# bmsMaster_main.net
KiCad netlist of a schematic drawn in Altium Designer
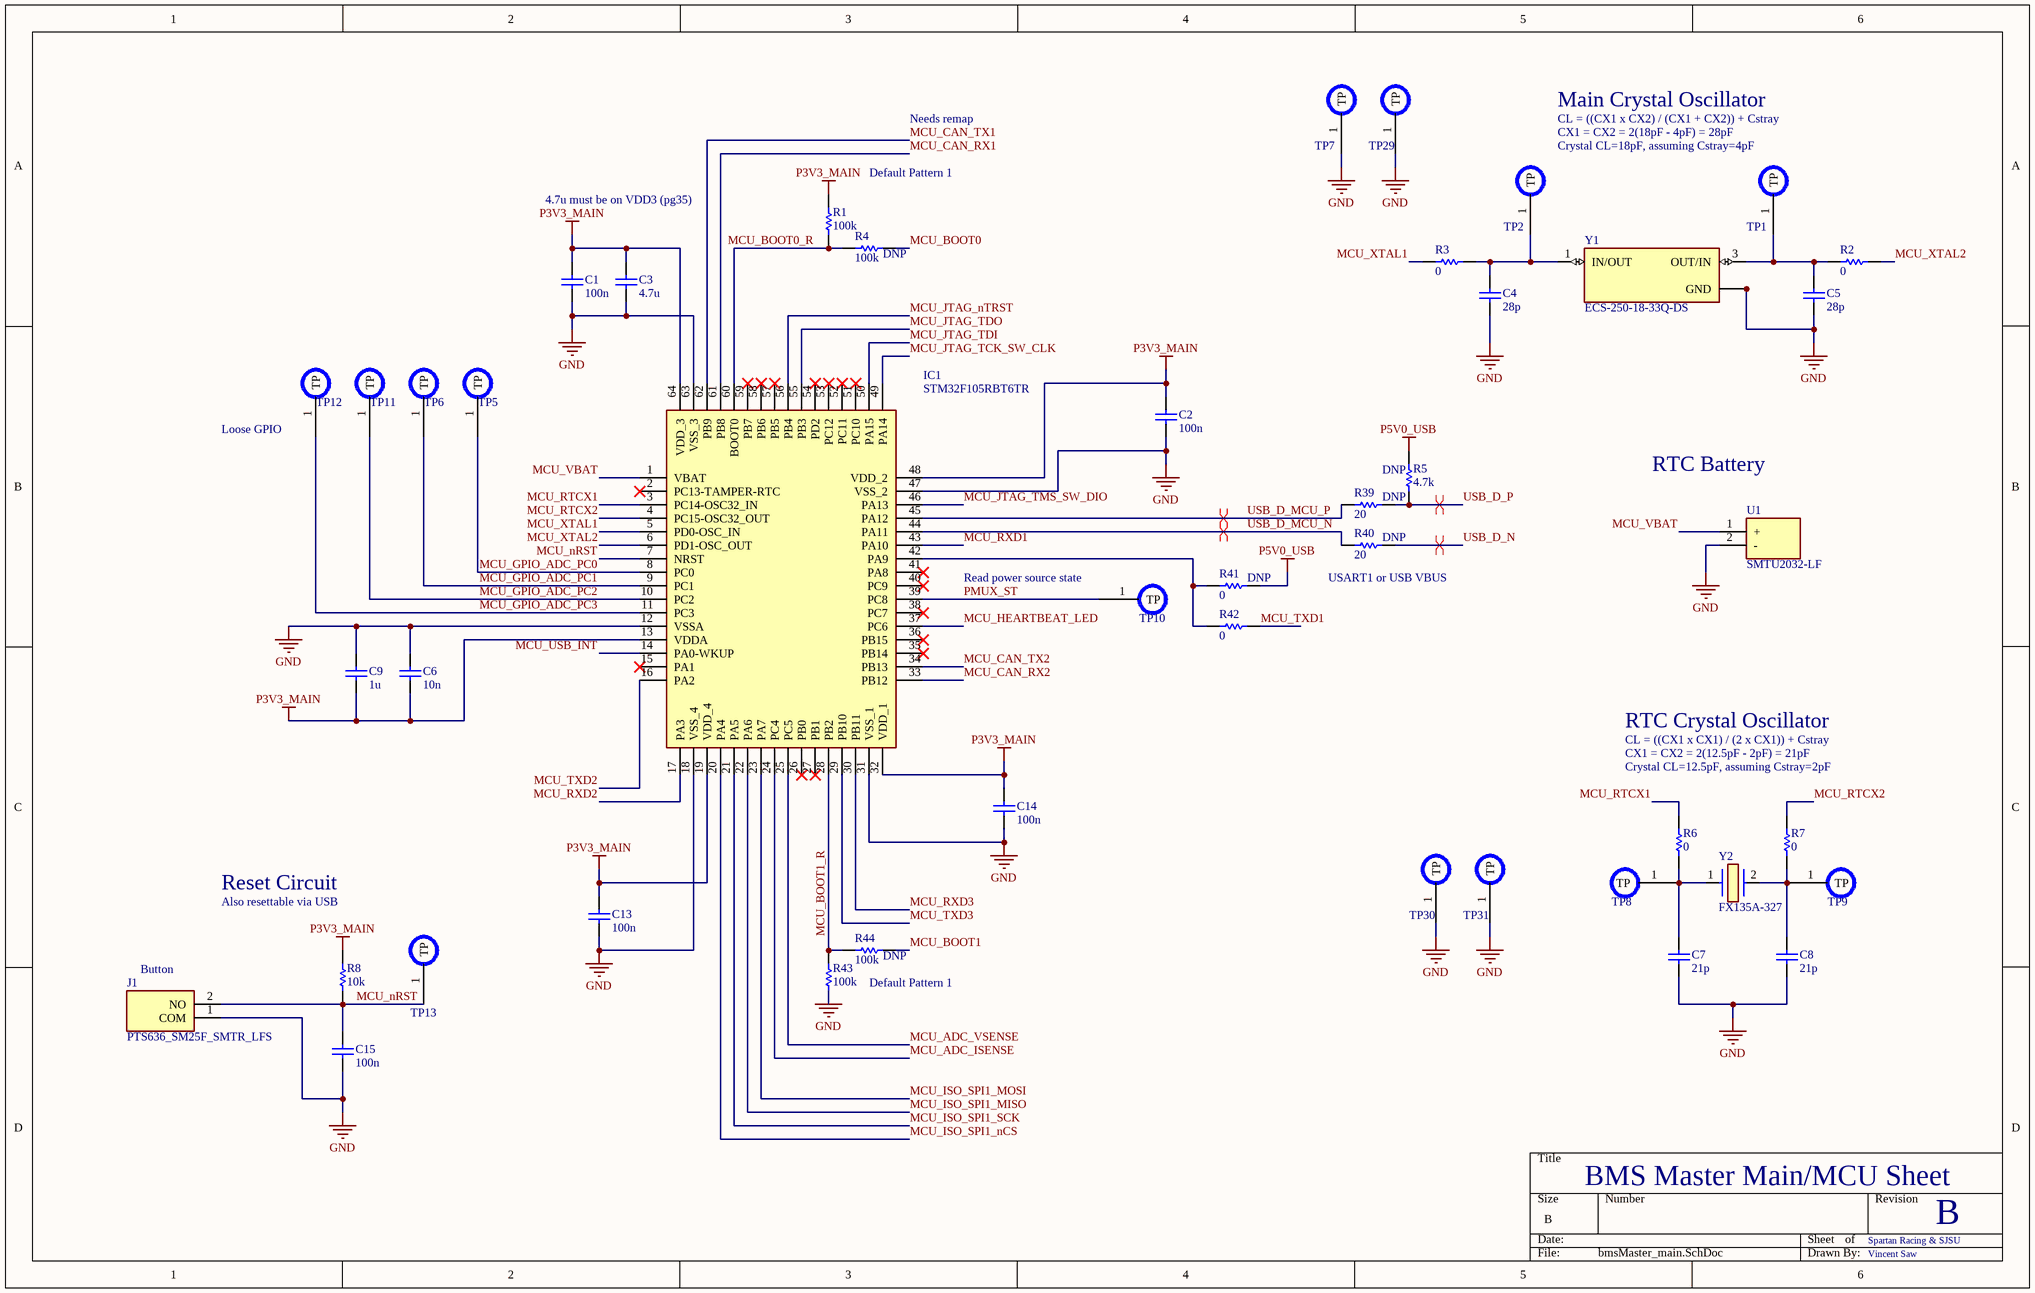
[diagram p0: bmsMaster_main.SchDoc]

(export (version "E")
  (design (tool "Eeschema 10.0.6"))
  (components
    (comp (ref "C1")
      (value "100n")
      (footprint "CAPC1608X90N")
      (description "Capacitor")
      (libsource (lib "Simulation Generic Components") (part "Capacitor"))
    )
    (comp (ref "C2")
      (value "100n")
      (footprint "CAPC1608X90N")
      (description "Capacitor")
      (libsource (lib "Simulation Generic Components") (part "Capacitor"))
    )
    (comp (ref "C3")
      (value "4.7u")
      (footprint "CAPC1608X90N")
      (description "Capacitor")
      (libsource (lib "Simulation Generic Components") (part "Capacitor"))
    )
    (comp (ref "C4")
      (value "28p")
      (footprint "CAPC1608X90N")
      (description "Capacitor")
      (libsource (lib "Simulation Generic Components") (part "Capacitor"))
    )
    (comp (ref "C5")
      (value "28p")
      (footprint "CAPC1608X90N")
      (description "Capacitor")
      (libsource (lib "Simulation Generic Components") (part "Capacitor"))
    )
    (comp (ref "C6")
      (value "10n")
      (footprint "CAPC1608X90N")
      (description "Capacitor")
      (libsource (lib "Simulation Generic Components") (part "Capacitor"))
    )
    (comp (ref "C7")
      (value "21p")
      (footprint "CAPC1608X90N")
      (description "Capacitor")
      (libsource (lib "Simulation Generic Components") (part "Capacitor"))
    )
    (comp (ref "C8")
      (value "21p")
      (footprint "CAPC1608X90N")
      (description "Capacitor")
      (libsource (lib "Simulation Generic Components") (part "Capacitor"))
    )
    (comp (ref "C9")
      (value "1u")
      (footprint "CAPC1608X90N")
      (description "Capacitor")
      (libsource (lib "Simulation Generic Components") (part "Capacitor"))
    )
    (comp (ref "C13")
      (value "100n")
      (footprint "CAPC1608X90N")
      (description "Capacitor")
      (libsource (lib "Simulation Generic Components") (part "Capacitor"))
    )
    (comp (ref "C14")
      (value "100n")
      (footprint "CAPC1608X90N")
      (description "Capacitor")
      (libsource (lib "Simulation Generic Components") (part "Capacitor"))
    )
    (comp (ref "C15")
      (value "100n")
      (footprint "CAPC1608X90N")
      (description "Capacitor")
      (libsource (lib "Simulation Generic Components") (part "Capacitor"))
    )
    (comp (ref "IC1")
      (value "STM32F105RBT6TR")
      (footprint "SamacSys:QFP50P1200X1200X160-64N")
      (description "Integrated Circuit")
      (fields (field (name "MOUSER PART NUMBER") "511-STM32F105RBT6TR"))
      (libsource (lib "*") (part "STM32F105RBT6TR"))
    )
    (comp (ref "J1")
      (value "PTS636_SM25F_SMTR_LFS")
      (footprint "SamacSys:PTS636SM25FSMTRLFS")
      (description "Connector")
      (fields
        (field (name "MANUFACTURER_PART_NUMBER") "PTS636 SM25F SMTR LFS")
        (field (name "MOUSER PART NUMBER") "611-PTS636SM25FSMTRL")
      )
      (libsource (lib "*") (part "PTS636_SM25F_SMTR_LFS"))
    )
    (comp (ref "R1")
      (value "100k")
      (footprint "RESC1608X50N")
      (description "Resistor")
      (libsource (lib "Simulation Generic Components") (part "Resistor"))
    )
    (comp (ref "R2")
      (value "0")
      (footprint "RESC1608X50N")
      (description "Resistor")
      (libsource (lib "Simulation Generic Components") (part "Resistor"))
    )
    (comp (ref "R3")
      (value "0")
      (footprint "RESC1608X50N")
      (description "Resistor")
      (libsource (lib "Simulation Generic Components") (part "Resistor"))
    )
    (comp (ref "R4")
      (value "100k")
      (footprint "RESC1608X50N")
      (description "Resistor")
      (libsource (lib "Simulation Generic Components") (part "Resistor"))
    )
    (comp (ref "R5")
      (value "4.7k")
      (footprint "RESC1608X50N")
      (description "Resistor")
      (libsource (lib "Simulation Generic Components") (part "Resistor"))
    )
    (comp (ref "R6")
      (value "0")
      (footprint "RESC1608X50N")
      (description "Resistor")
      (libsource (lib "Simulation Generic Components") (part "Resistor"))
    )
    (comp (ref "R7")
      (value "0")
      (footprint "RESC1608X50N")
      (description "Resistor")
      (libsource (lib "Simulation Generic Components") (part "Resistor"))
    )
    (comp (ref "R8")
      (value "10k")
      (footprint "RESC1608X50N")
      (description "Resistor")
      (libsource (lib "Simulation Generic Components") (part "Resistor"))
    )
    (comp (ref "R39")
      (value "20")
      (footprint "RESC1608X50N")
      (description "Resistor")
      (libsource (lib "Simulation Generic Components") (part "Resistor"))
    )
    (comp (ref "R40")
      (value "20")
      (footprint "RESC1608X50N")
      (description "Resistor")
      (libsource (lib "Simulation Generic Components") (part "Resistor"))
    )
    (comp (ref "R41")
      (value "0")
      (footprint "RESC1608X50N")
      (description "Resistor")
      (libsource (lib "Simulation Generic Components") (part "Resistor"))
    )
    (comp (ref "R42")
      (value "0")
      (footprint "RESC1608X50N")
      (description "Resistor")
      (libsource (lib "Simulation Generic Components") (part "Resistor"))
    )
    (comp (ref "R43")
      (value "100k")
      (footprint "RESC1608X50N")
      (description "Resistor")
      (libsource (lib "Simulation Generic Components") (part "Resistor"))
    )
    (comp (ref "R44")
      (value "100k")
      (footprint "RESC1608X50N")
      (description "Resistor")
      (libsource (lib "Simulation Generic Components") (part "Resistor"))
    )
    (comp (ref "TP1")
      (value "TSTPT")
      (footprint "Testpoint1")
      (libsource (lib "testpoint1") (part "Testpoint1"))
    )
    (comp (ref "TP2")
      (value "TSTPT")
      (footprint "Testpoint1")
      (libsource (lib "testpoint1") (part "Testpoint1"))
    )
    (comp (ref "TP5")
      (value "TSTPT")
      (footprint "Testpoint1")
      (libsource (lib "testpoint1") (part "Testpoint1"))
    )
    (comp (ref "TP6")
      (value "TSTPT")
      (footprint "Testpoint1")
      (libsource (lib "testpoint1") (part "Testpoint1"))
    )
    (comp (ref "TP7")
      (value "TSTPT")
      (footprint "Testpoint1")
      (libsource (lib "testpoint1") (part "Testpoint1"))
    )
    (comp (ref "TP8")
      (value "TSTPT")
      (footprint "Testpoint1")
      (libsource (lib "testpoint1") (part "Testpoint1"))
    )
    (comp (ref "TP9")
      (value "TSTPT")
      (footprint "Testpoint1")
      (libsource (lib "testpoint1") (part "Testpoint1"))
    )
    (comp (ref "TP10")
      (value "TSTPT")
      (footprint "Testpoint1")
      (libsource (lib "testpoint1") (part "Testpoint1"))
    )
    (comp (ref "TP11")
      (value "TSTPT")
      (footprint "Testpoint1")
      (libsource (lib "testpoint1") (part "Testpoint1"))
    )
    (comp (ref "TP12")
      (value "TSTPT")
      (footprint "Testpoint1")
      (libsource (lib "testpoint1") (part "Testpoint1"))
    )
    (comp (ref "TP13")
      (value "TSTPT")
      (footprint "Testpoint1")
      (libsource (lib "testpoint1") (part "Testpoint1"))
    )
    (comp (ref "TP29")
      (value "TSTPT")
      (footprint "Testpoint1")
      (libsource (lib "testpoint1") (part "Testpoint1"))
    )
    (comp (ref "TP30")
      (value "TSTPT")
      (footprint "Testpoint1")
      (libsource (lib "testpoint1") (part "Testpoint1"))
    )
    (comp (ref "TP31")
      (value "TSTPT")
      (footprint "Testpoint1")
      (libsource (lib "testpoint1") (part "Testpoint1"))
    )
    (comp (ref "U1")
      (value "SMTU2032-LF")
      (footprint "SamacSys:SMTU2032LF")
      (description "Undefined or Miscellaneous")
      (fields (field (name "MOUSER PART NUMBER") "614-SMTU2032-LF"))
      (libsource (lib "*") (part "SMTU2032-LF"))
    )
    (comp (ref "Y1")
      (value "ECS-250-18-33Q-DS")
      (footprint "ECS-250-18-33Q-DS:XTAL_ECS-250-18-33Q-DS")
      (fields (field (name "MF") "{'manufacturer': u'ECS Inc.'}"))
      (libsource (lib "*") (part "ECS-250-18-33Q-DS"))
    )
    (comp (ref "Y2")
      (value "FX135A-327")
      (footprint "SamacSys:FX135A327")
      (description "Crystal or Oscillator")
      (fields (field (name "MOUSER PART NUMBER") "559-FX135A-327"))
      (libsource (lib "*") (part "FX135A-327"))
    )
  )
  (nets
    (net (code "1") (name "/MCU_ADC_ISENSE") (class "Default")
      (node (ref "IC1") (pin "24") (pinfunction "PC4_24") (pintype "passive"))
    )
    (net (code "2") (name "/MCU_ADC_VSENSE") (class "Default")
      (node (ref "IC1") (pin "25") (pinfunction "PC5_25") (pintype "passive"))
    )
    (net (code "3") (name "/MCU_BOOT0") (class "Default")
      (node (ref "R4") (pin "2") (pinfunction "2_2") (pintype "passive"))
    )
    (net (code "4") (name "/MCU_BOOT0_R") (class "Default")
      (node (ref "IC1") (pin "60") (pinfunction "BOOT0_60") (pintype "passive"))
      (node (ref "R1") (pin "1") (pinfunction "1_1") (pintype "passive"))
      (node (ref "R4") (pin "1") (pinfunction "1_1") (pintype "passive"))
    )
    (net (code "5") (name "/MCU_BOOT1") (class "Default")
      (node (ref "R44") (pin "1") (pinfunction "1_1") (pintype "passive"))
    )
    (net (code "6") (name "/MCU_BOOT1_R") (class "Default")
      (node (ref "IC1") (pin "28") (pinfunction "PB2_28") (pintype "passive"))
      (node (ref "R43") (pin "1") (pinfunction "1_1") (pintype "passive"))
      (node (ref "R44") (pin "2") (pinfunction "2_2") (pintype "passive"))
    )
    (net (code "7") (name "/MCU_CAN_RX1") (class "Default")
      (node (ref "IC1") (pin "61") (pinfunction "PB8_61") (pintype "passive"))
    )
    (net (code "8") (name "/MCU_CAN_RX2") (class "Default")
      (node (ref "IC1") (pin "33") (pinfunction "PB12_33") (pintype "passive"))
    )
    (net (code "9") (name "/MCU_CAN_TX1") (class "Default")
      (node (ref "IC1") (pin "62") (pinfunction "PB9_62") (pintype "passive"))
    )
    (net (code "10") (name "/MCU_CAN_TX2") (class "Default")
      (node (ref "IC1") (pin "34") (pinfunction "PB13_34") (pintype "passive"))
    )
    (net (code "11") (name "/MCU_GPIO_ADC_PC0") (class "Default")
      (node (ref "IC1") (pin "8") (pinfunction "PC0_8") (pintype "passive"))
      (node (ref "TP5") (pin "1") (pinfunction "TP_1") (pintype "passive"))
    )
    (net (code "12") (name "/MCU_GPIO_ADC_PC1") (class "Default")
      (node (ref "IC1") (pin "9") (pinfunction "PC1_9") (pintype "passive"))
      (node (ref "TP6") (pin "1") (pinfunction "TP_1") (pintype "passive"))
    )
    (net (code "13") (name "/MCU_GPIO_ADC_PC2") (class "Default")
      (node (ref "IC1") (pin "10") (pinfunction "PC2_10") (pintype "passive"))
      (node (ref "TP11") (pin "1") (pinfunction "TP_1") (pintype "passive"))
    )
    (net (code "14") (name "/MCU_GPIO_ADC_PC3") (class "Default")
      (node (ref "IC1") (pin "11") (pinfunction "PC3_11") (pintype "passive"))
      (node (ref "TP12") (pin "1") (pinfunction "TP_1") (pintype "passive"))
    )
    (net (code "15") (name "/MCU_HEARTBEAT_LED") (class "Default")
      (node (ref "IC1") (pin "37") (pinfunction "PC6_37") (pintype "passive"))
    )
    (net (code "16") (name "/MCU_ISO_SPI1_MISO") (class "Default")
      (node (ref "IC1") (pin "22") (pinfunction "PA6_22") (pintype "passive"))
    )
    (net (code "17") (name "/MCU_ISO_SPI1_MOSI") (class "Default")
      (node (ref "IC1") (pin "23") (pinfunction "PA7_23") (pintype "passive"))
    )
    (net (code "18") (name "/MCU_ISO_SPI1_SCK") (class "Default")
      (node (ref "IC1") (pin "21") (pinfunction "PA5_21") (pintype "passive"))
    )
    (net (code "19") (name "/MCU_ISO_SPI1_nCS") (class "Default")
      (node (ref "IC1") (pin "20") (pinfunction "PA4_20") (pintype "passive"))
    )
    (net (code "20") (name "/MCU_JTAG_TCK_SW_CLK") (class "Default")
      (node (ref "IC1") (pin "49") (pinfunction "PA14_49") (pintype "passive"))
    )
    (net (code "21") (name "/MCU_JTAG_TDI") (class "Default")
      (node (ref "IC1") (pin "50") (pinfunction "PA15_50") (pintype "passive"))
    )
    (net (code "22") (name "/MCU_JTAG_TDO") (class "Default")
      (node (ref "IC1") (pin "55") (pinfunction "PB3_55") (pintype "passive"))
    )
    (net (code "23") (name "/MCU_JTAG_TMS_SW_DIO") (class "Default")
      (node (ref "IC1") (pin "46") (pinfunction "PA13_46") (pintype "passive"))
    )
    (net (code "24") (name "/MCU_JTAG_nTRST") (class "Default")
      (node (ref "IC1") (pin "56") (pinfunction "PB4_56") (pintype "passive"))
    )
    (net (code "25") (name "/MCU_RTCX1") (class "Default")
      (node (ref "IC1") (pin "3") (pinfunction "PC14-OSC32_IN_3") (pintype "passive"))
      (node (ref "R6") (pin "1") (pinfunction "1_1") (pintype "passive"))
    )
    (net (code "26") (name "/MCU_RTCX2") (class "Default")
      (node (ref "IC1") (pin "4") (pinfunction "PC15-OSC32_OUT_4") (pintype "passive"))
      (node (ref "R7") (pin "1") (pinfunction "1_1") (pintype "passive"))
    )
    (net (code "27") (name "/MCU_RXD1") (class "Default")
      (node (ref "IC1") (pin "43") (pinfunction "PA10_43") (pintype "passive"))
    )
    (net (code "28") (name "/MCU_RXD2") (class "Default")
      (node (ref "IC1") (pin "17") (pinfunction "PA3_17") (pintype "passive"))
    )
    (net (code "29") (name "/MCU_RXD3") (class "Default")
      (node (ref "IC1") (pin "30") (pinfunction "PB11_30") (pintype "passive"))
    )
    (net (code "30") (name "/MCU_TXD1") (class "Default")
      (node (ref "R42") (pin "2") (pinfunction "2_2") (pintype "passive"))
    )
    (net (code "31") (name "/MCU_TXD2") (class "Default")
      (node (ref "IC1") (pin "16") (pinfunction "PA2_16") (pintype "passive"))
    )
    (net (code "32") (name "/MCU_TXD3") (class "Default")
      (node (ref "IC1") (pin "29") (pinfunction "PB10_29") (pintype "passive"))
    )
    (net (code "33") (name "/MCU_USB_INT") (class "Default")
      (node (ref "IC1") (pin "14") (pinfunction "PA0-WKUP_14") (pintype "passive"))
    )
    (net (code "34") (name "/MCU_VBAT") (class "Default")
      (node (ref "IC1") (pin "1") (pinfunction "VBAT_1") (pintype "passive"))
      (node (ref "U1") (pin "1") (pinfunction "+_1") (pintype "passive"))
    )
    (net (code "35") (name "/MCU_XTAL1") (class "Default")
      (node (ref "IC1") (pin "5") (pinfunction "PD0-OSC_IN_5") (pintype "passive"))
      (node (ref "R3") (pin "2") (pinfunction "2_2") (pintype "passive"))
    )
    (net (code "36") (name "/MCU_XTAL2") (class "Default")
      (node (ref "IC1") (pin "6") (pinfunction "PD1-OSC_OUT_6") (pintype "passive"))
      (node (ref "R2") (pin "1") (pinfunction "1_1") (pintype "passive"))
    )
    (net (code "37") (name "/MCU_nRST") (class "Default")
      (node (ref "C15") (pin "2") (pinfunction "2_2") (pintype "passive"))
      (node (ref "IC1") (pin "7") (pinfunction "NRST_7") (pintype "passive"))
      (node (ref "J1") (pin "2") (pinfunction "NO_2") (pintype "passive"))
      (node (ref "R8") (pin "1") (pinfunction "1_1") (pintype "passive"))
      (node (ref "TP13") (pin "1") (pinfunction "TP_1") (pintype "passive"))
    )
    (net (code "38") (name "/PMUX_ST") (class "Default")
      (node (ref "IC1") (pin "39") (pinfunction "PC8_39") (pintype "passive"))
      (node (ref "TP10") (pin "1") (pinfunction "TP_1") (pintype "passive"))
    )
    (net (code "39") (name "/USB_D_MCU_N") (class "Default")
      (node (ref "IC1") (pin "44") (pinfunction "PA11_44") (pintype "passive"))
      (node (ref "R40") (pin "1") (pinfunction "1_1") (pintype "passive"))
    )
    (net (code "40") (name "/USB_D_MCU_P") (class "Default")
      (node (ref "IC1") (pin "45") (pinfunction "PA12_45") (pintype "passive"))
      (node (ref "R39") (pin "1") (pinfunction "1_1") (pintype "passive"))
    )
    (net (code "41") (name "/USB_D_N") (class "Default")
      (node (ref "R40") (pin "2") (pinfunction "2_2") (pintype "passive"))
    )
    (net (code "42") (name "/USB_D_P") (class "Default")
      (node (ref "R39") (pin "2") (pinfunction "2_2") (pintype "passive"))
      (node (ref "R5") (pin "1") (pinfunction "1_1") (pintype "passive"))
    )
    (net (code "43") (name "GND") (class "Default")
      (node (ref "C1") (pin "1") (pinfunction "1_1") (pintype "passive"))
      (node (ref "C13") (pin "1") (pinfunction "1_1") (pintype "passive"))
      (node (ref "C14") (pin "1") (pinfunction "1_1") (pintype "passive"))
      (node (ref "C15") (pin "1") (pinfunction "1_1") (pintype "passive"))
      (node (ref "C2") (pin "1") (pinfunction "1_1") (pintype "passive"))
      (node (ref "C3") (pin "1") (pinfunction "1_1") (pintype "passive"))
      (node (ref "C4") (pin "1") (pinfunction "1_1") (pintype "passive"))
      (node (ref "C5") (pin "1") (pinfunction "1_1") (pintype "passive"))
      (node (ref "C6") (pin "2") (pinfunction "2_2") (pintype "passive"))
      (node (ref "C7") (pin "1") (pinfunction "1_1") (pintype "passive"))
      (node (ref "C8") (pin "1") (pinfunction "1_1") (pintype "passive"))
      (node (ref "C9") (pin "2") (pinfunction "2_2") (pintype "passive"))
      (node (ref "IC1") (pin "12") (pinfunction "VSSA_12") (pintype "passive"))
      (node (ref "IC1") (pin "18") (pinfunction "VSS_4_18") (pintype "passive"))
      (node (ref "IC1") (pin "31") (pinfunction "VSS_1_31") (pintype "passive"))
      (node (ref "IC1") (pin "47") (pinfunction "VSS_2_47") (pintype "passive"))
      (node (ref "IC1") (pin "63") (pinfunction "VSS_3_63") (pintype "passive"))
      (node (ref "J1") (pin "1") (pinfunction "COM_1") (pintype "passive"))
      (node (ref "R43") (pin "2") (pinfunction "2_2") (pintype "passive"))
      (node (ref "TP29") (pin "1") (pinfunction "TP_1") (pintype "passive"))
      (node (ref "TP30") (pin "1") (pinfunction "TP_1") (pintype "passive"))
      (node (ref "TP31") (pin "1") (pinfunction "TP_1") (pintype "passive"))
      (node (ref "TP7") (pin "1") (pinfunction "TP_1") (pintype "passive"))
      (node (ref "U1") (pin "2") (pinfunction "-_2") (pintype "passive"))
      (node (ref "Y1") (pin "2") (pinfunction "GND_2") (pintype "power_in"))
      (node (ref "Y1") (pin "4") (pinfunction "GND_4") (pintype "power_in"))
    )
    (net (code "44") (name "Net-(IC1-PA9)") (class "Default")
      (node (ref "IC1") (pin "42") (pinfunction "PA9_42") (pintype "passive"))
      (node (ref "R41") (pin "1") (pinfunction "1_1") (pintype "passive"))
      (node (ref "R42") (pin "1") (pinfunction "1_1") (pintype "passive"))
    )
    (net (code "45") (name "Net-(TP1-TP)") (class "Default")
      (node (ref "C5") (pin "2") (pinfunction "2_2") (pintype "passive"))
      (node (ref "R2") (pin "2") (pinfunction "2_2") (pintype "passive"))
      (node (ref "TP1") (pin "1") (pinfunction "TP_1") (pintype "passive"))
      (node (ref "Y1") (pin "3") (pinfunction "OUT/IN_3") (pintype "bidirectional"))
    )
    (net (code "46") (name "Net-(TP2-TP)") (class "Default")
      (node (ref "C4") (pin "2") (pinfunction "2_2") (pintype "passive"))
      (node (ref "R3") (pin "1") (pinfunction "1_1") (pintype "passive"))
      (node (ref "TP2") (pin "1") (pinfunction "TP_1") (pintype "passive"))
      (node (ref "Y1") (pin "1") (pinfunction "IN/OUT_1") (pintype "bidirectional"))
    )
    (net (code "47") (name "Net-(TP8-TP)") (class "Default")
      (node (ref "C7") (pin "2") (pinfunction "2_2") (pintype "passive"))
      (node (ref "R6") (pin "2") (pinfunction "2_2") (pintype "passive"))
      (node (ref "TP8") (pin "1") (pinfunction "TP_1") (pintype "passive"))
      (node (ref "Y2") (pin "1") (pinfunction "1_1") (pintype "passive"))
    )
    (net (code "48") (name "Net-(TP9-TP)") (class "Default")
      (node (ref "C8") (pin "2") (pinfunction "2_2") (pintype "passive"))
      (node (ref "R7") (pin "2") (pinfunction "2_2") (pintype "passive"))
      (node (ref "TP9") (pin "1") (pinfunction "TP_1") (pintype "passive"))
      (node (ref "Y2") (pin "2") (pinfunction "2_2") (pintype "passive"))
    )
    (net (code "49") (name "P3V3_MAIN") (class "Default")
      (node (ref "C1") (pin "2") (pinfunction "2_2") (pintype "passive"))
      (node (ref "C13") (pin "2") (pinfunction "2_2") (pintype "passive"))
      (node (ref "C14") (pin "2") (pinfunction "2_2") (pintype "passive"))
      (node (ref "C2") (pin "2") (pinfunction "2_2") (pintype "passive"))
      (node (ref "C3") (pin "2") (pinfunction "2_2") (pintype "passive"))
      (node (ref "C6") (pin "1") (pinfunction "1_1") (pintype "passive"))
      (node (ref "C9") (pin "1") (pinfunction "1_1") (pintype "passive"))
      (node (ref "IC1") (pin "13") (pinfunction "VDDA_13") (pintype "passive"))
      (node (ref "IC1") (pin "19") (pinfunction "VDD_4_19") (pintype "passive"))
      (node (ref "IC1") (pin "32") (pinfunction "VDD_1_32") (pintype "passive"))
      (node (ref "IC1") (pin "48") (pinfunction "VDD_2_48") (pintype "passive"))
      (node (ref "IC1") (pin "64") (pinfunction "VDD_3_64") (pintype "passive"))
      (node (ref "R1") (pin "2") (pinfunction "2_2") (pintype "passive"))
      (node (ref "R8") (pin "2") (pinfunction "2_2") (pintype "passive"))
    )
    (net (code "50") (name "P5V0_USB") (class "Default")
      (node (ref "R41") (pin "2") (pinfunction "2_2") (pintype "passive"))
      (node (ref "R5") (pin "2") (pinfunction "2_2") (pintype "passive"))
    )
    (net (code "51") (name "unconnected-(IC1-PA1-Pad15)") (class "Default")
      (node (ref "IC1") (pin "15") (pinfunction "PA1_15") (pintype "passive+no_connect"))
    )
    (net (code "52") (name "unconnected-(IC1-PA8-Pad41)") (class "Default")
      (node (ref "IC1") (pin "41") (pinfunction "PA8_41") (pintype "passive+no_connect"))
    )
    (net (code "53") (name "unconnected-(IC1-PB0-Pad26)") (class "Default")
      (node (ref "IC1") (pin "26") (pinfunction "PB0_26") (pintype "passive+no_connect"))
    )
    (net (code "54") (name "unconnected-(IC1-PB1-Pad27)") (class "Default")
      (node (ref "IC1") (pin "27") (pinfunction "PB1_27") (pintype "passive+no_connect"))
    )
    (net (code "55") (name "unconnected-(IC1-PB5-Pad57)") (class "Default")
      (node (ref "IC1") (pin "57") (pinfunction "PB5_57") (pintype "passive+no_connect"))
    )
    (net (code "56") (name "unconnected-(IC1-PB6-Pad58)") (class "Default")
      (node (ref "IC1") (pin "58") (pinfunction "PB6_58") (pintype "passive+no_connect"))
    )
    (net (code "57") (name "unconnected-(IC1-PB7-Pad59)") (class "Default")
      (node (ref "IC1") (pin "59") (pinfunction "PB7_59") (pintype "passive+no_connect"))
    )
    (net (code "58") (name "unconnected-(IC1-PB14-Pad35)") (class "Default")
      (node (ref "IC1") (pin "35") (pinfunction "PB14_35") (pintype "passive+no_connect"))
    )
    (net (code "59") (name "unconnected-(IC1-PB15-Pad36)") (class "Default")
      (node (ref "IC1") (pin "36") (pinfunction "PB15_36") (pintype "passive+no_connect"))
    )
    (net (code "60") (name "unconnected-(IC1-PC7-Pad38)") (class "Default")
      (node (ref "IC1") (pin "38") (pinfunction "PC7_38") (pintype "passive+no_connect"))
    )
    (net (code "61") (name "unconnected-(IC1-PC9-Pad40)") (class "Default")
      (node (ref "IC1") (pin "40") (pinfunction "PC9_40") (pintype "passive+no_connect"))
    )
    (net (code "62") (name "unconnected-(IC1-PC10-Pad51)") (class "Default")
      (node (ref "IC1") (pin "51") (pinfunction "PC10_51") (pintype "passive+no_connect"))
    )
    (net (code "63") (name "unconnected-(IC1-PC11-Pad52)") (class "Default")
      (node (ref "IC1") (pin "52") (pinfunction "PC11_52") (pintype "passive+no_connect"))
    )
    (net (code "64") (name "unconnected-(IC1-PC12-Pad53)") (class "Default")
      (node (ref "IC1") (pin "53") (pinfunction "PC12_53") (pintype "passive+no_connect"))
    )
    (net (code "65") (name "unconnected-(IC1-PC13-TAMPER-RTC-Pad2)") (class "Default")
      (node (ref "IC1") (pin "2") (pinfunction "PC13-TAMPER-RTC_2") (pintype "passive+no_connect"))
    )
    (net (code "66") (name "unconnected-(IC1-PD2-Pad54)") (class "Default")
      (node (ref "IC1") (pin "54") (pinfunction "PD2_54") (pintype "passive+no_connect"))
    )
  )
)
